# Attiny85_Blinking_Led_FIS2018.net
KiCad netlist of a schematic drawn in EAGLE
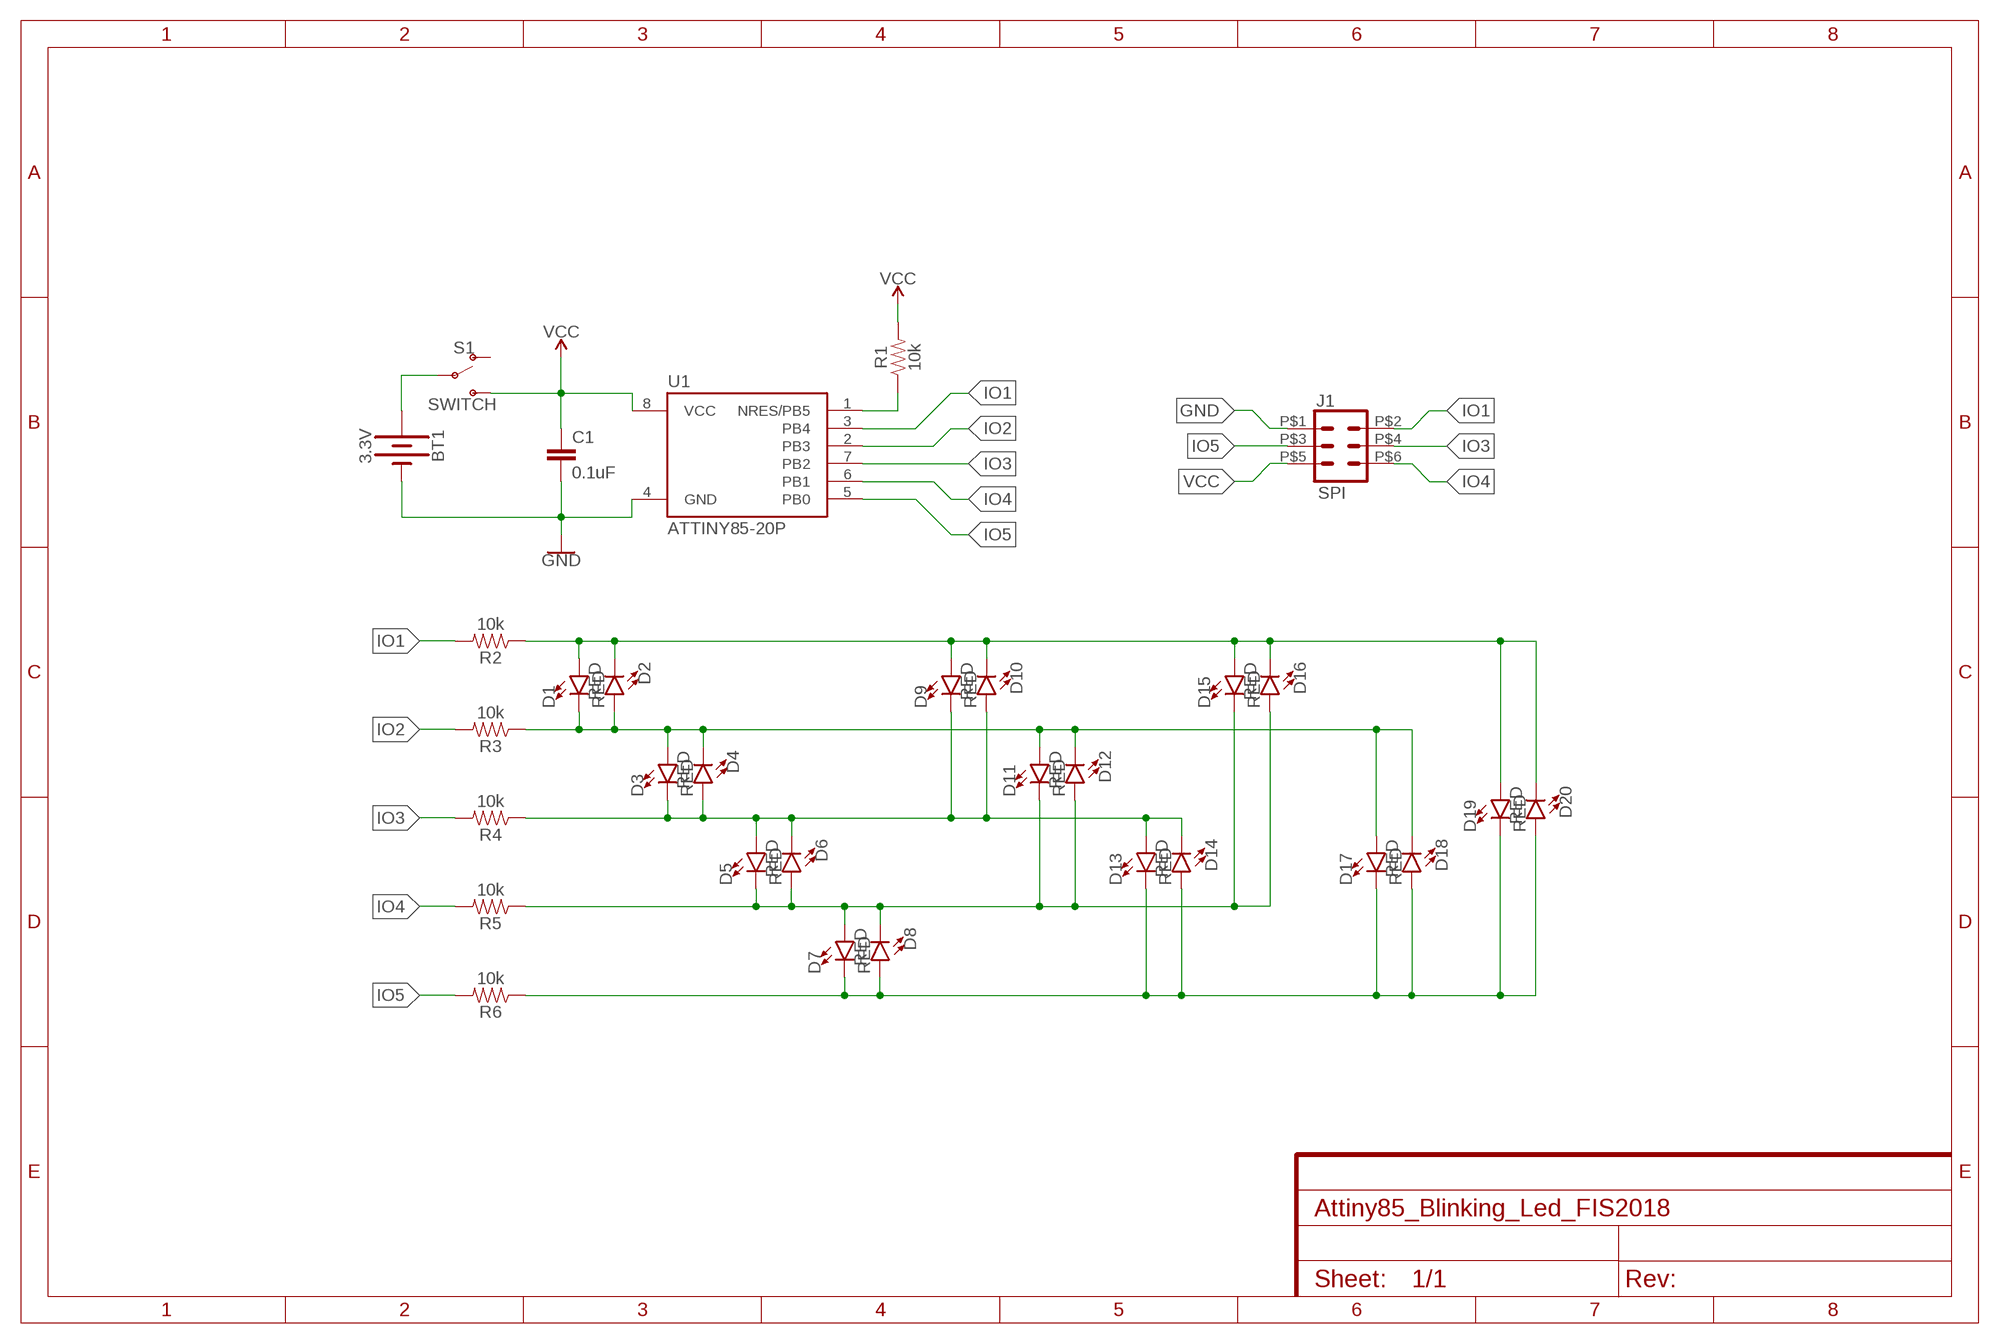
[diagram p0: schematic, sheet 1]

(export (version "E")
  (design (tool "Eeschema 10.0.6"))
  (components
    (comp (ref "BT1")
      (value "3.3V")
      (footprint "eagle-import:BATTCON_20MM_4LEGS")
      (libsource (lib "eagle-import") (part "BATTERY-20MM_SMD_4LEGS"))
    )
    (comp (ref "C1")
      (value "0.1uF")
      (footprint "eagle-import:0603")
      (libsource (lib "eagle-import") (part "0.1UF-0603-25V-(+80/-20%)"))
    )
    (comp (ref "D1")
      (value "RED")
      (footprint "eagle-import:LED_3MM")
      (libsource (lib "eagle-import") (part "LED3MM"))
    )
    (comp (ref "D2")
      (value "RED")
      (footprint "eagle-import:LED_3MM")
      (libsource (lib "eagle-import") (part "LED3MM"))
    )
    (comp (ref "D3")
      (value "RED")
      (footprint "eagle-import:LED_3MM")
      (libsource (lib "eagle-import") (part "LED3MM"))
    )
    (comp (ref "D4")
      (value "RED")
      (footprint "eagle-import:LED_3MM")
      (libsource (lib "eagle-import") (part "LED3MM"))
    )
    (comp (ref "D5")
      (value "RED")
      (footprint "eagle-import:LED_3MM")
      (libsource (lib "eagle-import") (part "LED3MM"))
    )
    (comp (ref "D6")
      (value "RED")
      (footprint "eagle-import:LED_3MM")
      (libsource (lib "eagle-import") (part "LED3MM"))
    )
    (comp (ref "D7")
      (value "RED")
      (footprint "eagle-import:LED_3MM")
      (libsource (lib "eagle-import") (part "LED3MM"))
    )
    (comp (ref "D8")
      (value "RED")
      (footprint "eagle-import:LED_3MM")
      (libsource (lib "eagle-import") (part "LED3MM"))
    )
    (comp (ref "D9")
      (value "RED")
      (footprint "eagle-import:LED_3MM")
      (libsource (lib "eagle-import") (part "LED3MM"))
    )
    (comp (ref "D10")
      (value "RED")
      (footprint "eagle-import:LED_3MM")
      (libsource (lib "eagle-import") (part "LED3MM"))
    )
    (comp (ref "D11")
      (value "RED")
      (footprint "eagle-import:LED_3MM")
      (libsource (lib "eagle-import") (part "LED3MM"))
    )
    (comp (ref "D12")
      (value "RED")
      (footprint "eagle-import:LED_3MM")
      (libsource (lib "eagle-import") (part "LED3MM"))
    )
    (comp (ref "D13")
      (value "RED")
      (footprint "eagle-import:LED_3MM")
      (libsource (lib "eagle-import") (part "LED3MM"))
    )
    (comp (ref "D14")
      (value "RED")
      (footprint "eagle-import:LED_3MM")
      (libsource (lib "eagle-import") (part "LED3MM"))
    )
    (comp (ref "D15")
      (value "RED")
      (footprint "eagle-import:LED_3MM")
      (libsource (lib "eagle-import") (part "LED3MM"))
    )
    (comp (ref "D16")
      (value "RED")
      (footprint "eagle-import:LED_3MM")
      (libsource (lib "eagle-import") (part "LED3MM"))
    )
    (comp (ref "D17")
      (value "RED")
      (footprint "eagle-import:LED_3MM")
      (libsource (lib "eagle-import") (part "LED3MM"))
    )
    (comp (ref "D18")
      (value "RED")
      (footprint "eagle-import:LED_3MM")
      (libsource (lib "eagle-import") (part "LED3MM"))
    )
    (comp (ref "D19")
      (value "RED")
      (footprint "eagle-import:LED_3MM")
      (libsource (lib "eagle-import") (part "LED3MM"))
    )
    (comp (ref "D20")
      (value "RED")
      (footprint "eagle-import:LED_3MM")
      (libsource (lib "eagle-import") (part "LED3MM"))
    )
    (comp (ref "J1")
      (value "SPI")
      (footprint "eagle-import:2X3_POGO")
      (libsource (lib "eagle-import") (part "CONN_03X2POGO_PINS"))
    )
    (comp (ref "R1")
      (value "10k")
      (footprint "eagle-import:AXIAL-0.3")
      (libsource (lib "eagle-import") (part "10KOHM-HORIZ-1/4W-1%"))
    )
    (comp (ref "R2")
      (value "10k")
      (footprint "eagle-import:AXIAL-0.3")
      (libsource (lib "eagle-import") (part "10KOHM-HORIZ-1/4W-1%"))
    )
    (comp (ref "R3")
      (value "10k")
      (footprint "eagle-import:AXIAL-0.3")
      (libsource (lib "eagle-import") (part "10KOHM-HORIZ-1/4W-1%"))
    )
    (comp (ref "R4")
      (value "10k")
      (footprint "eagle-import:AXIAL-0.3")
      (libsource (lib "eagle-import") (part "10KOHM-HORIZ-1/4W-1%"))
    )
    (comp (ref "R5")
      (value "10k")
      (footprint "eagle-import:AXIAL-0.3")
      (libsource (lib "eagle-import") (part "10KOHM-HORIZ-1/4W-1%"))
    )
    (comp (ref "R6")
      (value "10k")
      (footprint "eagle-import:AXIAL-0.3")
      (libsource (lib "eagle-import") (part "10KOHM-HORIZ-1/4W-1%"))
    )
    (comp (ref "S1")
      (value "SWITCH")
      (footprint "eagle-import:SWITCH_SPST_SMD_A")
      (libsource (lib "eagle-import") (part "SWITCH-SPDT-SMD-RIGHT-ANGLE"))
    )
    (comp (ref "U1")
      (value "ATTINY85-20P")
      (footprint "eagle-import:PDIP08_300MIL")
      (libsource (lib "eagle-import") (part "ATTINY85P-20"))
    )
  )
  (nets
    (net (code "1") (name "GND") (class "Default")
      (node (ref "BT1") (pin "NEGATIVE") (pinfunction "-_NEGATIVE") (pintype "power_in"))
      (node (ref "C1") (pin "2") (pinfunction "2_2") (pintype "passive"))
      (node (ref "J1") (pin "P$1") (pinfunction "1_P$1") (pintype "bidirectional"))
      (node (ref "U1") (pin "4") (pinfunction "GND_4") (pintype "power_in"))
    )
    (net (code "2") (name "IO1") (class "Default")
      (node (ref "J1") (pin "P$2") (pinfunction "2_P$2") (pintype "bidirectional"))
      (node (ref "R2") (pin "P$2") (pinfunction "2_P$2") (pintype "passive"))
      (node (ref "U1") (pin "3") (pinfunction "PB4_3") (pintype "bidirectional"))
    )
    (net (code "3") (name "IO2") (class "Default")
      (node (ref "R3") (pin "P$2") (pinfunction "2_P$2") (pintype "passive"))
      (node (ref "U1") (pin "2") (pinfunction "PB3_2") (pintype "bidirectional"))
    )
    (net (code "4") (name "IO3") (class "Default")
      (node (ref "J1") (pin "P$4") (pinfunction "4_P$4") (pintype "bidirectional"))
      (node (ref "R4") (pin "P$2") (pinfunction "2_P$2") (pintype "passive"))
      (node (ref "U1") (pin "7") (pinfunction "PB2_7") (pintype "bidirectional"))
    )
    (net (code "5") (name "IO4") (class "Default")
      (node (ref "J1") (pin "P$6") (pinfunction "6_P$6") (pintype "bidirectional"))
      (node (ref "R5") (pin "P$2") (pinfunction "2_P$2") (pintype "passive"))
      (node (ref "U1") (pin "6") (pinfunction "PB1_6") (pintype "bidirectional"))
    )
    (net (code "6") (name "IO5") (class "Default")
      (node (ref "J1") (pin "P$3") (pinfunction "3_P$3") (pintype "bidirectional"))
      (node (ref "R6") (pin "P$2") (pinfunction "2_P$2") (pintype "passive"))
      (node (ref "U1") (pin "5") (pinfunction "PB0_5") (pintype "bidirectional"))
    )
    (net (code "7") (name "Net-(D1-C)") (class "Default")
      (node (ref "D1") (pin "K") (pinfunction "C_K") (pintype "passive"))
      (node (ref "D11") (pin "A") (pinfunction "A_A") (pintype "passive"))
      (node (ref "D12") (pin "K") (pinfunction "C_K") (pintype "passive"))
      (node (ref "D17") (pin "A") (pinfunction "A_A") (pintype "passive"))
      (node (ref "D18") (pin "K") (pinfunction "C_K") (pintype "passive"))
      (node (ref "D2") (pin "A") (pinfunction "A_A") (pintype "passive"))
      (node (ref "D3") (pin "A") (pinfunction "A_A") (pintype "passive"))
      (node (ref "D4") (pin "K") (pinfunction "C_K") (pintype "passive"))
      (node (ref "R3") (pin "P$1") (pinfunction "1_P$1") (pintype "passive"))
    )
    (net (code "8") (name "Net-(D10-C)") (class "Default")
      (node (ref "D1") (pin "A") (pinfunction "A_A") (pintype "passive"))
      (node (ref "D10") (pin "K") (pinfunction "C_K") (pintype "passive"))
      (node (ref "D15") (pin "A") (pinfunction "A_A") (pintype "passive"))
      (node (ref "D16") (pin "K") (pinfunction "C_K") (pintype "passive"))
      (node (ref "D19") (pin "A") (pinfunction "A_A") (pintype "passive"))
      (node (ref "D2") (pin "K") (pinfunction "C_K") (pintype "passive"))
      (node (ref "D20") (pin "K") (pinfunction "C_K") (pintype "passive"))
      (node (ref "D9") (pin "A") (pinfunction "A_A") (pintype "passive"))
      (node (ref "R2") (pin "P$1") (pinfunction "1_P$1") (pintype "passive"))
    )
    (net (code "9") (name "Net-(D11-C)") (class "Default")
      (node (ref "D11") (pin "K") (pinfunction "C_K") (pintype "passive"))
      (node (ref "D12") (pin "A") (pinfunction "A_A") (pintype "passive"))
      (node (ref "D15") (pin "K") (pinfunction "C_K") (pintype "passive"))
      (node (ref "D16") (pin "A") (pinfunction "A_A") (pintype "passive"))
      (node (ref "D5") (pin "K") (pinfunction "C_K") (pintype "passive"))
      (node (ref "D6") (pin "A") (pinfunction "A_A") (pintype "passive"))
      (node (ref "D7") (pin "A") (pinfunction "A_A") (pintype "passive"))
      (node (ref "D8") (pin "K") (pinfunction "C_K") (pintype "passive"))
      (node (ref "R5") (pin "P$1") (pinfunction "1_P$1") (pintype "passive"))
    )
    (net (code "10") (name "Net-(D13-C)") (class "Default")
      (node (ref "D13") (pin "K") (pinfunction "C_K") (pintype "passive"))
      (node (ref "D14") (pin "A") (pinfunction "A_A") (pintype "passive"))
      (node (ref "D17") (pin "K") (pinfunction "C_K") (pintype "passive"))
      (node (ref "D18") (pin "A") (pinfunction "A_A") (pintype "passive"))
      (node (ref "D19") (pin "K") (pinfunction "C_K") (pintype "passive"))
      (node (ref "D20") (pin "A") (pinfunction "A_A") (pintype "passive"))
      (node (ref "D7") (pin "K") (pinfunction "C_K") (pintype "passive"))
      (node (ref "D8") (pin "A") (pinfunction "A_A") (pintype "passive"))
      (node (ref "R6") (pin "P$1") (pinfunction "1_P$1") (pintype "passive"))
    )
    (net (code "11") (name "Net-(D14-C)") (class "Default")
      (node (ref "D10") (pin "A") (pinfunction "A_A") (pintype "passive"))
      (node (ref "D13") (pin "A") (pinfunction "A_A") (pintype "passive"))
      (node (ref "D14") (pin "K") (pinfunction "C_K") (pintype "passive"))
      (node (ref "D3") (pin "K") (pinfunction "C_K") (pintype "passive"))
      (node (ref "D4") (pin "A") (pinfunction "A_A") (pintype "passive"))
      (node (ref "D5") (pin "A") (pinfunction "A_A") (pintype "passive"))
      (node (ref "D6") (pin "K") (pinfunction "C_K") (pintype "passive"))
      (node (ref "D9") (pin "K") (pinfunction "C_K") (pintype "passive"))
      (node (ref "R4") (pin "P$1") (pinfunction "1_P$1") (pintype "passive"))
    )
    (net (code "12") (name "Net-(R1-1)") (class "Default")
      (node (ref "R1") (pin "P$1") (pinfunction "1_P$1") (pintype "passive"))
      (node (ref "U1") (pin "1") (pinfunction "NRES/PB5_1") (pintype "bidirectional"))
    )
    (net (code "13") (name "Net-(S1-P)") (class "Default")
      (node (ref "BT1") (pin "POSITIVE@1") (pinfunction "+_POSITIVE@1") (pintype "power_in"))
      (node (ref "BT1") (pin "POSITIVE@2") (pinfunction "+_POSITIVE@2") (pintype "power_in"))
      (node (ref "BT1") (pin "POSITIVE@3") (pinfunction "+_POSITIVE@3") (pintype "power_in"))
      (node (ref "BT1") (pin "POSITIVE@4") (pinfunction "+_POSITIVE@4") (pintype "power_in"))
      (node (ref "S1") (pin "2") (pinfunction "P_2") (pintype "passive"))
    )
    (net (code "14") (name "VCC") (class "Default")
      (node (ref "C1") (pin "1") (pinfunction "1_1") (pintype "passive"))
      (node (ref "J1") (pin "P$5") (pinfunction "5_P$5") (pintype "bidirectional"))
      (node (ref "R1") (pin "P$2") (pinfunction "2_P$2") (pintype "passive"))
      (node (ref "S1") (pin "3") (pinfunction "S_3") (pintype "passive"))
      (node (ref "U1") (pin "8") (pinfunction "VCC_8") (pintype "power_in"))
    )
    (net (code "15") (name "unconnected-(S1-O-Pad1)") (class "Default")
      (node (ref "S1") (pin "1") (pinfunction "O_1") (pintype "passive"))
    )
  )
)
